# Case-Hack-PCB.net
KiCad netlist of a schematic drawn in EAGLE
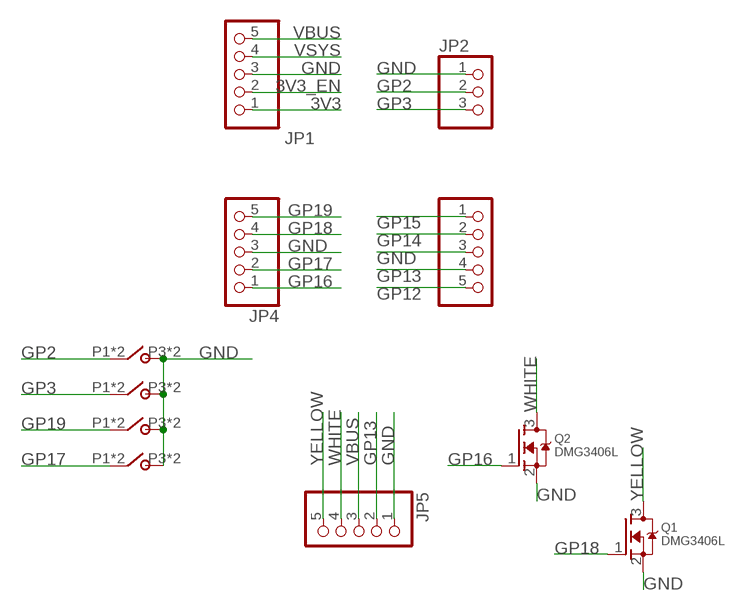
[diagram p0: schematic, sheet 1]

(export (version "E")
  (design (tool "Eeschema 10.0.6"))
  (components
    (comp (ref "JP1")
      (value "HEADER-1X5ROUND")
      (footprint "eagle-import:1X05_ROUND")
      (libsource (lib "eagle-import") (part "HEADER-1X5ROUND"))
    )
    (comp (ref "JP2")
      (value "HEADER-1X3ROUND")
      (footprint "eagle-import:1X03_ROUND")
      (libsource (lib "eagle-import") (part "HEADER-1X3ROUND"))
    )
    (comp (ref "JP3")
      (value "HEADER-1X5ROUND")
      (footprint "eagle-import:1X05_ROUND")
      (libsource (lib "eagle-import") (part "HEADER-1X5ROUND"))
    )
    (comp (ref "JP4")
      (value "HEADER-1X5ROUND")
      (footprint "eagle-import:1X05_ROUND")
      (libsource (lib "eagle-import") (part "HEADER-1X5ROUND"))
    )
    (comp (ref "JP5")
      (value "HEADER-1X5ROUND")
      (footprint "eagle-import:1X05_ROUND")
      (libsource (lib "eagle-import") (part "HEADER-1X5ROUND"))
    )
    (comp (ref "Q1")
      (value "DMG3406L")
      (footprint "eagle-import:SOT23-WIDE")
      (libsource (lib "eagle-import") (part "MOSFET-NWIDE"))
    )
    (comp (ref "Q2")
      (value "DMG3406L")
      (footprint "eagle-import:SOT23-WIDE")
      (libsource (lib "eagle-import") (part "MOSFET-NWIDE"))
    )
    (comp (ref "U$1")
      (value "K2-1109SP-B4SA-01")
      (footprint "eagle-import:K2-1109SP-B4SA-01")
      (libsource (lib "eagle-import") (part "K2-1109SP-B4SA-01"))
    )
    (comp (ref "U$2")
      (value "K2-1109SP-B4SA-01")
      (footprint "eagle-import:K2-1109SP-B4SA-01")
      (libsource (lib "eagle-import") (part "K2-1109SP-B4SA-01"))
    )
    (comp (ref "U$3")
      (value "K2-1109SP-B4SA-01")
      (footprint "eagle-import:K2-1109SP-B4SA-01")
      (libsource (lib "eagle-import") (part "K2-1109SP-B4SA-01"))
    )
    (comp (ref "U$4")
      (value "K2-1109SP-B4SA-01")
      (footprint "eagle-import:K2-1109SP-B4SA-01")
      (libsource (lib "eagle-import") (part "K2-1109SP-B4SA-01"))
    )
  )
  (nets
    (net (code "1") (name "/3V3") (class "Default")
      (node (ref "JP1") (pin "1") (pinfunction "1_1") (pintype "passive"))
    )
    (net (code "2") (name "/3V3_EN") (class "Default")
      (node (ref "JP1") (pin "2") (pinfunction "2_2") (pintype "passive"))
    )
    (net (code "3") (name "/GND") (class "Default")
      (node (ref "JP1") (pin "3") (pinfunction "3_3") (pintype "passive"))
      (node (ref "JP2") (pin "1") (pinfunction "1_1") (pintype "passive"))
      (node (ref "JP3") (pin "3") (pinfunction "3_3") (pintype "passive"))
      (node (ref "JP4") (pin "3") (pinfunction "3_3") (pintype "passive"))
      (node (ref "JP5") (pin "1") (pinfunction "1_1") (pintype "passive"))
      (node (ref "Q1") (pin "2") (pinfunction "S_2") (pintype "bidirectional"))
      (node (ref "Q2") (pin "2") (pinfunction "S_2") (pintype "bidirectional"))
      (node (ref "U$1") (pin "P3") (pinfunction "P$2_P3") (pintype "bidirectional"))
      (node (ref "U$1") (pin "P4") (pinfunction "P$2_P4") (pintype "bidirectional"))
      (node (ref "U$2") (pin "P3") (pinfunction "P$2_P3") (pintype "bidirectional"))
      (node (ref "U$2") (pin "P4") (pinfunction "P$2_P4") (pintype "bidirectional"))
      (node (ref "U$3") (pin "P3") (pinfunction "P$2_P3") (pintype "bidirectional"))
      (node (ref "U$3") (pin "P4") (pinfunction "P$2_P4") (pintype "bidirectional"))
      (node (ref "U$4") (pin "P3") (pinfunction "P$2_P3") (pintype "bidirectional"))
      (node (ref "U$4") (pin "P4") (pinfunction "P$2_P4") (pintype "bidirectional"))
    )
    (net (code "4") (name "/GP2") (class "Default")
      (node (ref "JP2") (pin "2") (pinfunction "2_2") (pintype "passive"))
      (node (ref "U$1") (pin "P1") (pinfunction "P$1_P1") (pintype "bidirectional"))
      (node (ref "U$1") (pin "P2") (pinfunction "P$1_P2") (pintype "bidirectional"))
    )
    (net (code "5") (name "/GP3") (class "Default")
      (node (ref "JP2") (pin "3") (pinfunction "3_3") (pintype "passive"))
      (node (ref "U$2") (pin "P1") (pinfunction "P$1_P1") (pintype "bidirectional"))
      (node (ref "U$2") (pin "P2") (pinfunction "P$1_P2") (pintype "bidirectional"))
    )
    (net (code "6") (name "/GP12") (class "Default")
      (node (ref "JP3") (pin "5") (pinfunction "5_5") (pintype "passive"))
    )
    (net (code "7") (name "/GP13") (class "Default")
      (node (ref "JP3") (pin "4") (pinfunction "4_4") (pintype "passive"))
      (node (ref "JP5") (pin "2") (pinfunction "2_2") (pintype "passive"))
    )
    (net (code "8") (name "/GP14") (class "Default")
      (node (ref "JP3") (pin "2") (pinfunction "2_2") (pintype "passive"))
    )
    (net (code "9") (name "/GP15") (class "Default")
      (node (ref "JP3") (pin "1") (pinfunction "1_1") (pintype "passive"))
    )
    (net (code "10") (name "/GP16") (class "Default")
      (node (ref "JP4") (pin "1") (pinfunction "1_1") (pintype "passive"))
      (node (ref "Q2") (pin "1") (pinfunction "G_1") (pintype "bidirectional"))
    )
    (net (code "11") (name "/GP17") (class "Default")
      (node (ref "JP4") (pin "2") (pinfunction "2_2") (pintype "passive"))
      (node (ref "U$4") (pin "P1") (pinfunction "P$1_P1") (pintype "bidirectional"))
      (node (ref "U$4") (pin "P2") (pinfunction "P$1_P2") (pintype "bidirectional"))
    )
    (net (code "12") (name "/GP18") (class "Default")
      (node (ref "JP4") (pin "4") (pinfunction "4_4") (pintype "passive"))
      (node (ref "Q1") (pin "1") (pinfunction "G_1") (pintype "bidirectional"))
    )
    (net (code "13") (name "/GP19") (class "Default")
      (node (ref "JP4") (pin "5") (pinfunction "5_5") (pintype "passive"))
      (node (ref "U$3") (pin "P1") (pinfunction "P$1_P1") (pintype "bidirectional"))
      (node (ref "U$3") (pin "P2") (pinfunction "P$1_P2") (pintype "bidirectional"))
    )
    (net (code "14") (name "/VBUS") (class "Default")
      (node (ref "JP1") (pin "5") (pinfunction "5_5") (pintype "passive"))
      (node (ref "JP5") (pin "3") (pinfunction "3_3") (pintype "passive"))
    )
    (net (code "15") (name "/VSYS") (class "Default")
      (node (ref "JP1") (pin "4") (pinfunction "4_4") (pintype "passive"))
    )
    (net (code "16") (name "/WHITE") (class "Default")
      (node (ref "JP5") (pin "4") (pinfunction "4_4") (pintype "passive"))
      (node (ref "Q2") (pin "3") (pinfunction "D_3") (pintype "bidirectional"))
    )
    (net (code "17") (name "/YELLOW") (class "Default")
      (node (ref "JP5") (pin "5") (pinfunction "5_5") (pintype "passive"))
      (node (ref "Q1") (pin "3") (pinfunction "D_3") (pintype "bidirectional"))
    )
  )
)
